# STM32F407VET6.net
KiCad netlist of a schematic drawn in Altium Designer
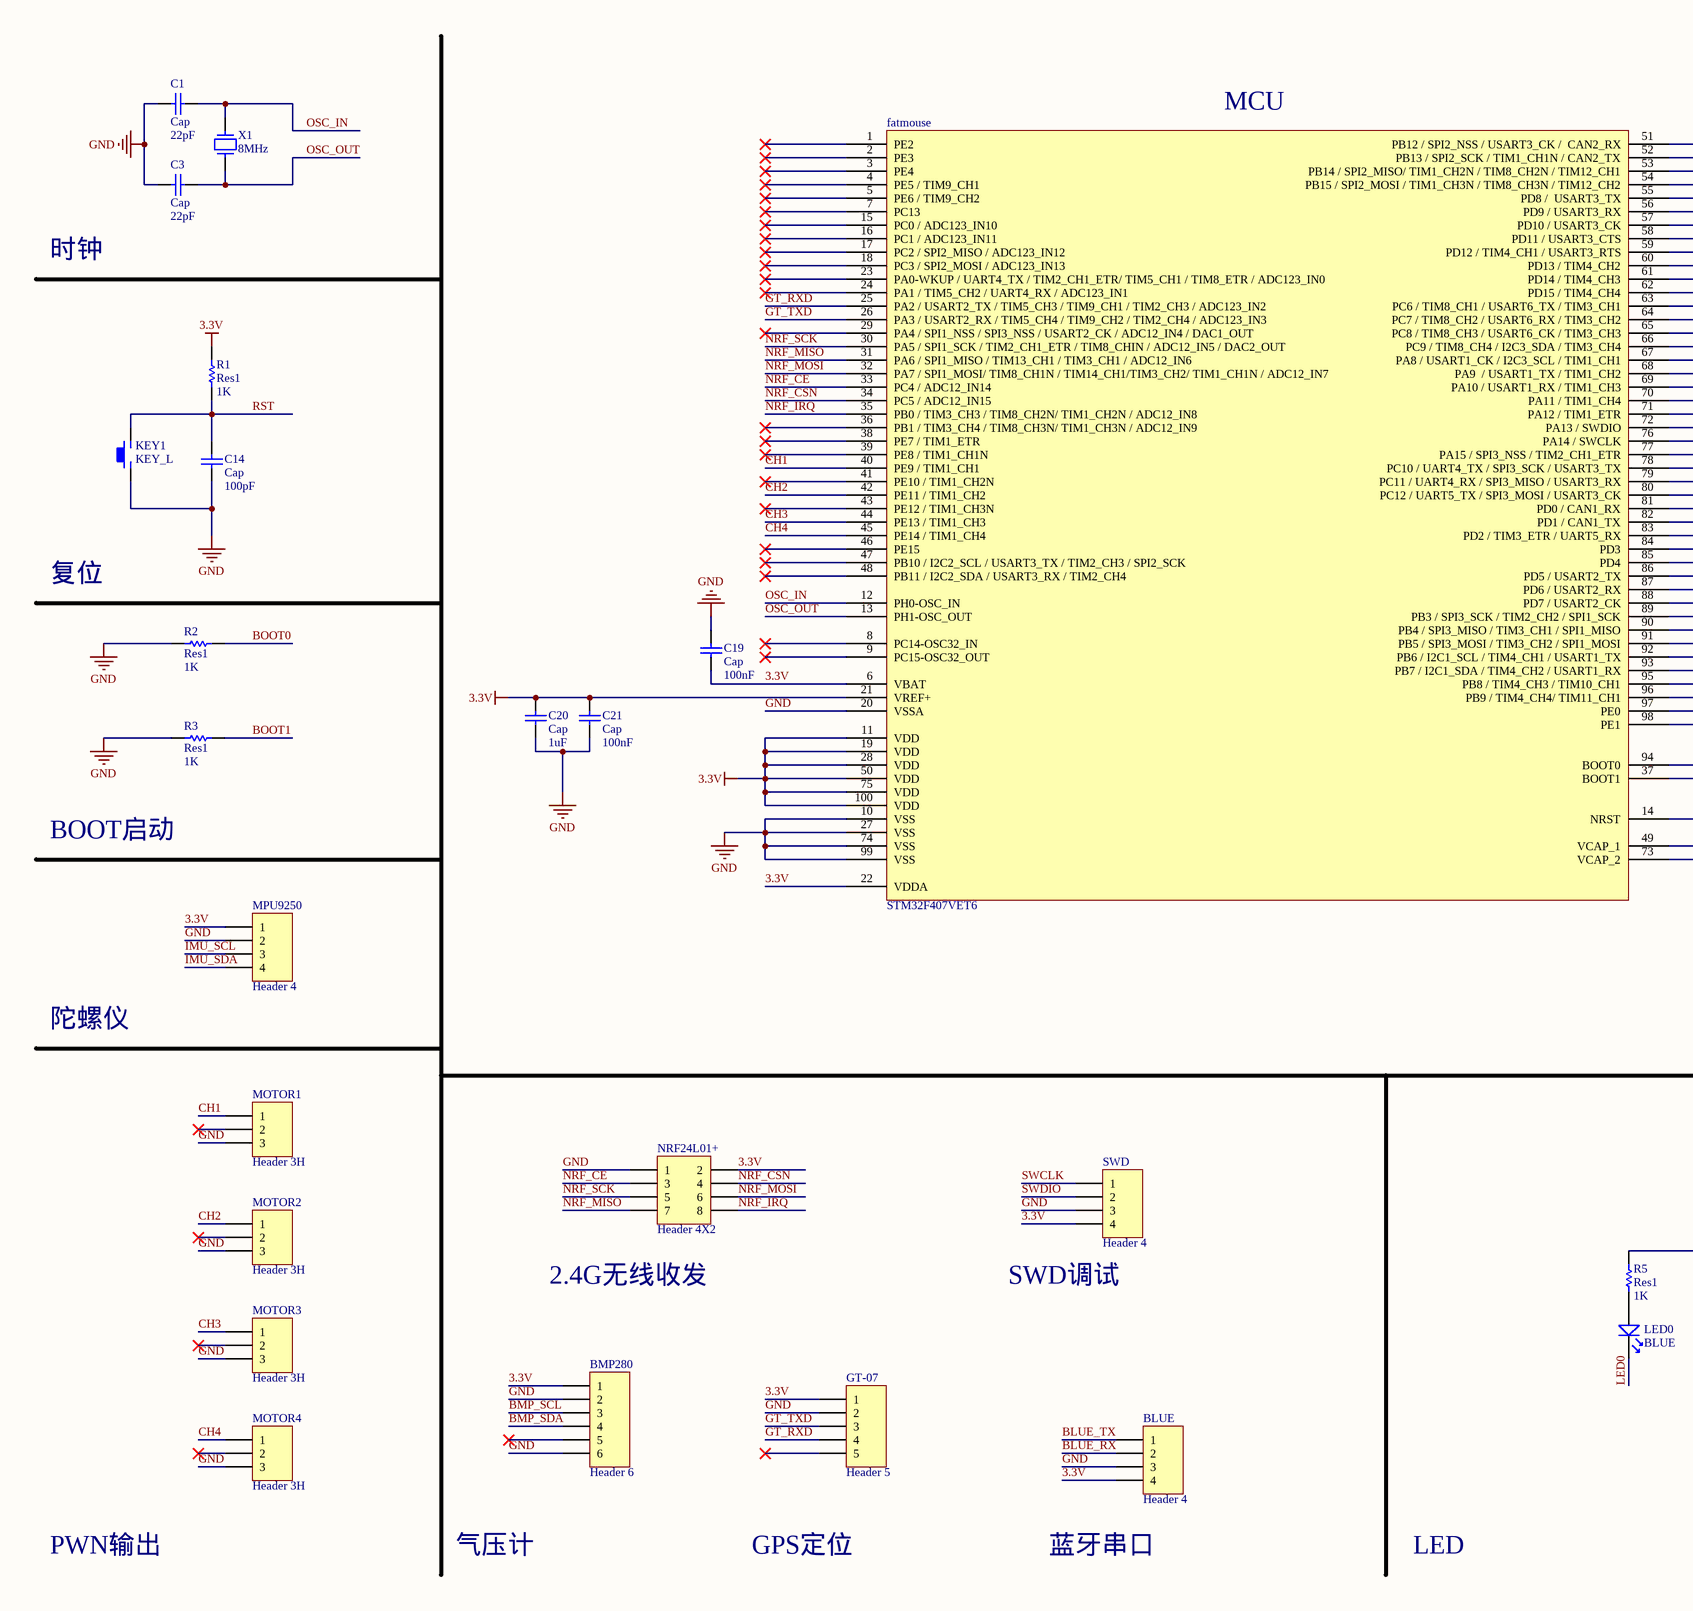
[diagram p0: STM32F407VET6.SchDoc, left]
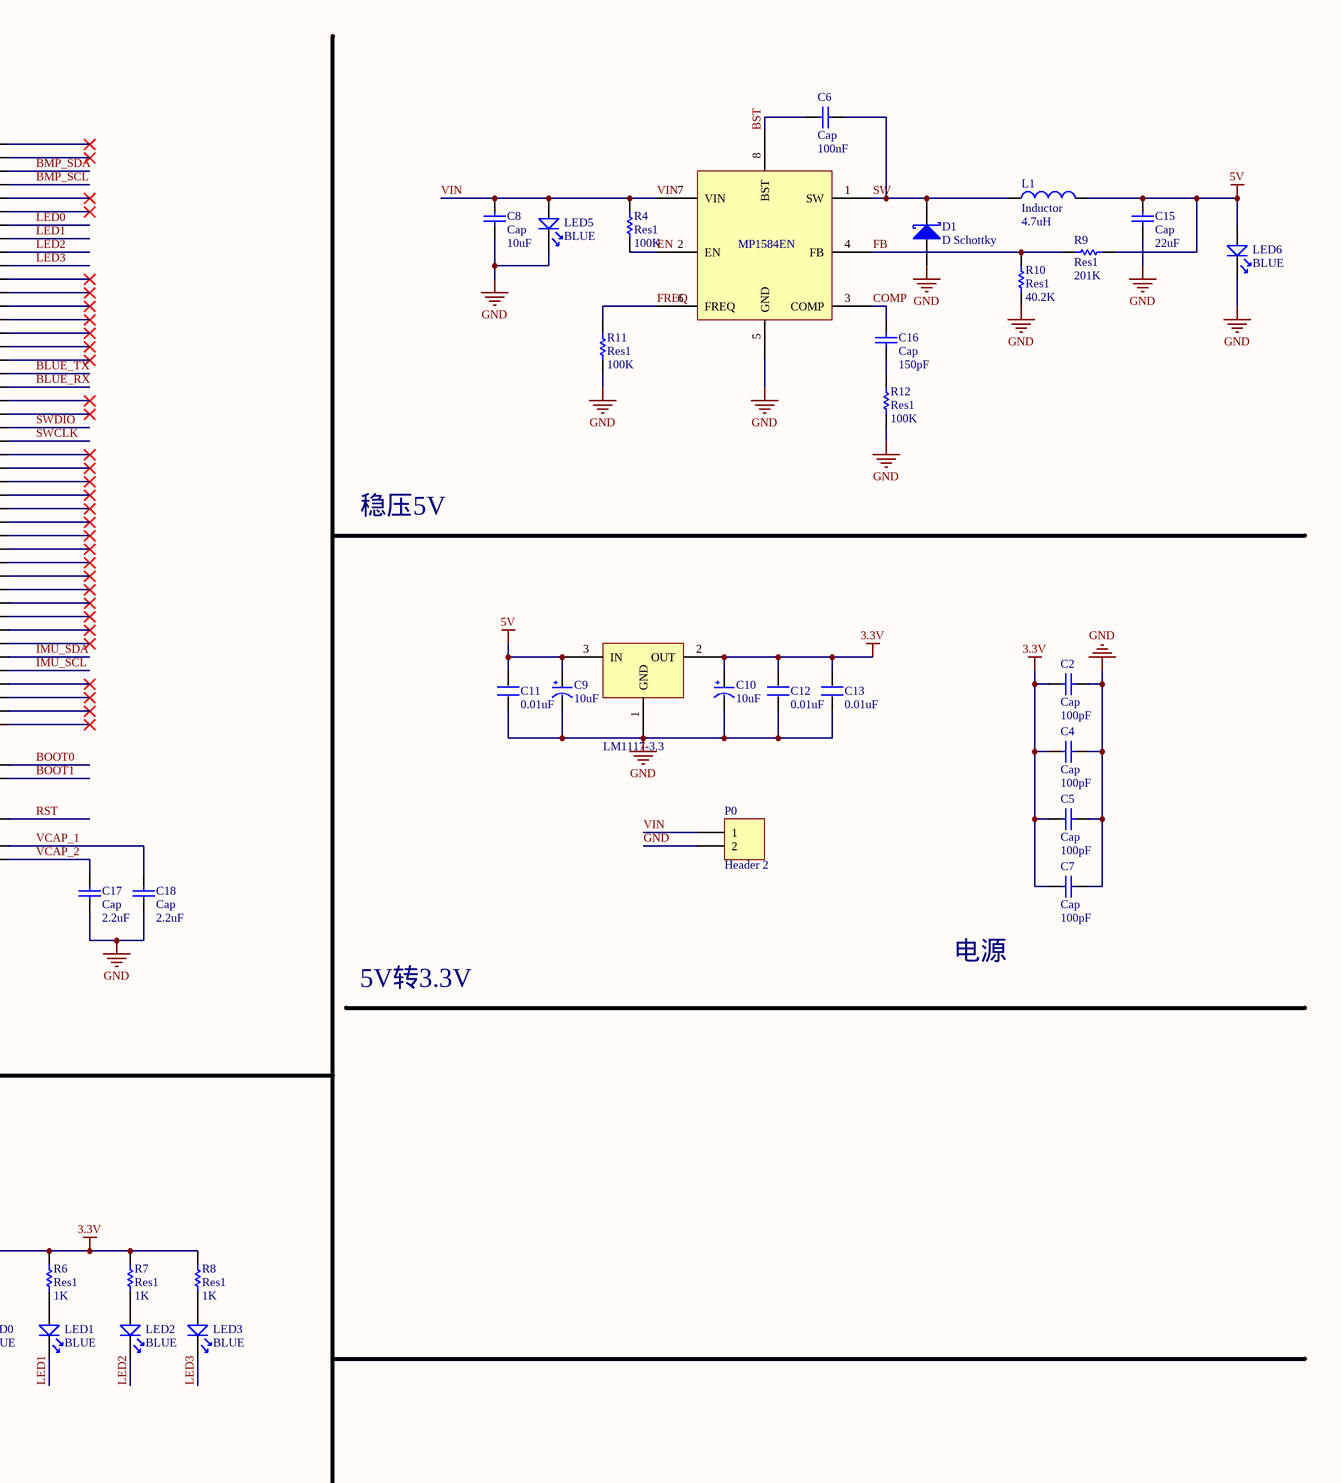
[diagram p1: STM32F407VET6.SchDoc, right]

(export (version "E")
  (design (tool "Eeschema 10.0.6"))
  (components
    (comp (ref "5V-3.3V")
      (value "LM1117-3.3")
      (footprint "SOT223_M")
      (libsource (lib "QUA") (part "LM1117-3.3"))
    )
    (comp (ref "BLUE")
      (value "Header 4")
      (footprint "PIN-4-2.54-1.0")
      (description "Header, 4-Pin")
      (fields (field (name "PUBLISHER") "Altium Limited"))
      (libsource (lib "Miscellaneous Connectors") (part "Header 4"))
    )
    (comp (ref "BMP280")
      (value "Header 6")
      (footprint "HDR1X6")
      (description "Header, 6-Pin")
      (fields (field (name "PUBLISHER") "Altium Limited"))
      (libsource (lib "Miscellaneous Connectors") (part "Header 6"))
    )
    (comp (ref "C1")
      (value "Cap")
      (footprint "C 0805")
      (description "Capacitor")
      (fields (field (name "ALTIUM_VALUE") "22pF") (field (name "PUBLISHER") "Altium Limited"))
      (libsource (lib "Miscellaneous Devices") (part "Cap"))
    )
    (comp (ref "C2")
      (value "Cap")
      (footprint "C 0805")
      (description "Capacitor")
      (fields (field (name "ALTIUM_VALUE") "100pF") (field (name "PUBLISHER") "Altium Limited"))
      (libsource (lib "Miscellaneous Devices") (part "Cap"))
    )
    (comp (ref "C3")
      (value "Cap")
      (footprint "C 0805")
      (description "Capacitor")
      (fields (field (name "ALTIUM_VALUE") "22pF") (field (name "PUBLISHER") "Altium Limited"))
      (libsource (lib "Miscellaneous Devices") (part "Cap"))
    )
    (comp (ref "C4")
      (value "Cap")
      (footprint "C 0805")
      (description "Capacitor")
      (fields (field (name "ALTIUM_VALUE") "100pF") (field (name "PUBLISHER") "Altium Limited"))
      (libsource (lib "Miscellaneous Devices") (part "Cap"))
    )
    (comp (ref "C5")
      (value "Cap")
      (footprint "C 0805")
      (description "Capacitor")
      (fields (field (name "ALTIUM_VALUE") "100pF") (field (name "PUBLISHER") "Altium Limited"))
      (libsource (lib "Miscellaneous Devices") (part "Cap"))
    )
    (comp (ref "C6")
      (value "Cap")
      (footprint "C 0805")
      (description "Capacitor")
      (fields (field (name "ALTIUM_VALUE") "100nF") (field (name "PUBLISHER") "Altium Limited"))
      (libsource (lib "Miscellaneous Devices") (part "Cap"))
    )
    (comp (ref "C7")
      (value "Cap")
      (footprint "C 0805")
      (description "Capacitor")
      (fields (field (name "ALTIUM_VALUE") "100pF") (field (name "PUBLISHER") "Altium Limited"))
      (libsource (lib "Miscellaneous Devices") (part "Cap"))
    )
    (comp (ref "C8")
      (value "Cap")
      (footprint "C 0805")
      (description "Capacitor")
      (fields (field (name "ALTIUM_VALUE") "10uF") (field (name "PUBLISHER") "Altium Limited"))
      (libsource (lib "Miscellaneous Devices") (part "Cap"))
    )
    (comp (ref "C9") (value "10uF") (footprint "CD A(3216)") (libsource (lib "REMOTOR V1.6") (part "CAP")))
    (comp (ref "C10") (value "10uF") (footprint "CD A(3216)") (libsource (lib "REMOTOR V1.6") (part "CAP")))
    (comp (ref "C11") (value "0.01uF") (footprint "C 0805") (libsource (lib "REMOTOR V1.6") (part "C")))
    (comp (ref "C12") (value "0.01uF") (footprint "C 0805") (libsource (lib "REMOTOR V1.6") (part "C")))
    (comp (ref "C13") (value "0.01uF") (footprint "C 0805") (libsource (lib "REMOTOR V1.6") (part "C")))
    (comp (ref "C14")
      (value "Cap")
      (footprint "C 0805")
      (description "Capacitor")
      (fields (field (name "ALTIUM_VALUE") "100pF") (field (name "PUBLISHER") "Altium Limited"))
      (libsource (lib "Miscellaneous Devices") (part "Cap"))
    )
    (comp (ref "C15")
      (value "Cap")
      (footprint "C 0805")
      (description "Capacitor")
      (fields (field (name "ALTIUM_VALUE") "22uF") (field (name "PUBLISHER") "Altium Limited"))
      (libsource (lib "Miscellaneous Devices") (part "Cap"))
    )
    (comp (ref "C16")
      (value "Cap")
      (footprint "C 0805")
      (description "Capacitor")
      (fields (field (name "ALTIUM_VALUE") "150pF") (field (name "PUBLISHER") "Altium Limited"))
      (libsource (lib "Miscellaneous Devices") (part "Cap"))
    )
    (comp (ref "C17")
      (value "Cap")
      (footprint "C 0805")
      (description "Capacitor")
      (fields (field (name "ALTIUM_VALUE") "2.2uF") (field (name "PUBLISHER") "Altium Limited"))
      (libsource (lib "Miscellaneous Devices") (part "Cap"))
    )
    (comp (ref "C18")
      (value "Cap")
      (footprint "C 0805")
      (description "Capacitor")
      (fields (field (name "ALTIUM_VALUE") "2.2uF") (field (name "PUBLISHER") "Altium Limited"))
      (libsource (lib "Miscellaneous Devices") (part "Cap"))
    )
    (comp (ref "C19")
      (value "Cap")
      (footprint "C 0805")
      (description "Capacitor")
      (fields (field (name "ALTIUM_VALUE") "100nF") (field (name "PUBLISHER") "Altium Limited"))
      (libsource (lib "Miscellaneous Devices") (part "Cap"))
    )
    (comp (ref "C20")
      (value "Cap")
      (footprint "C 0805")
      (description "Capacitor")
      (fields (field (name "ALTIUM_VALUE") "1uF") (field (name "PUBLISHER") "Altium Limited"))
      (libsource (lib "Miscellaneous Devices") (part "Cap"))
    )
    (comp (ref "C21")
      (value "Cap")
      (footprint "C 0805")
      (description "Capacitor")
      (fields (field (name "ALTIUM_VALUE") "100nF") (field (name "PUBLISHER") "Altium Limited"))
      (libsource (lib "Miscellaneous Devices") (part "Cap"))
    )
    (comp (ref "D1")
      (value "D Schottky")
      (footprint "SMA")
      (description "Schottky Diode")
      (fields (field (name "PUBLISHER") "Altium Limited"))
      (libsource (lib "Miscellaneous Devices") (part "D Schottky"))
    )
    (comp (ref "fatmouse")
      (value "STM32F407VET6")
      (footprint "QFP-100-0.5")
      (libsource (lib "QUA") (part "STM32F407VET6"))
    )
    (comp (ref "GT-07")
      (value "Header 5")
      (footprint "HDR1X5")
      (description "Header, 5-Pin")
      (fields (field (name "PUBLISHER") "Altium Limited"))
      (libsource (lib "Miscellaneous Connectors") (part "Header 5"))
    )
    (comp (ref "KEY1") (value "KEY_L") (footprint "key") (libsource (lib "REMOTOR V1.6") (part "KEY")))
    (comp (ref "L1")
      (value "Inductor")
      (footprint "CDRH74")
      (fields (field (name "ALTIUM_VALUE") "4.7uH") (field (name "PUBLISHER") "Altium Limited"))
      (libsource (lib "Miscellaneous Devices") (part "Inductor"))
    )
    (comp (ref "LED0") (value "BLUE") (footprint "LED-0805") (libsource (lib "REMOTOR V1.6") (part "LED")))
    (comp (ref "LED1") (value "BLUE") (footprint "LED-0805") (libsource (lib "REMOTOR V1.6") (part "LED")))
    (comp (ref "LED2") (value "BLUE") (footprint "LED-0805") (libsource (lib "REMOTOR V1.6") (part "LED")))
    (comp (ref "LED3") (value "BLUE") (footprint "LED-0805") (libsource (lib "REMOTOR V1.6") (part "LED")))
    (comp (ref "LED5") (value "BLUE") (footprint "LED-0805") (libsource (lib "REMOTOR V1.6") (part "LED")))
    (comp (ref "LED6") (value "BLUE") (footprint "LED-0805") (libsource (lib "REMOTOR V1.6") (part "LED")))
    (comp (ref "MOTOR1")
      (value "Header 3H")
      (footprint "HDR1X3H")
      (description "Header, 3-Pin, Right Angle")
      (fields (field (name "PUBLISHER") "Altium Limited"))
      (libsource (lib "Miscellaneous Connectors") (part "Header 3H"))
    )
    (comp (ref "MOTOR2")
      (value "Header 3H")
      (footprint "HDR1X3H")
      (description "Header, 3-Pin, Right Angle")
      (fields (field (name "PUBLISHER") "Altium Limited"))
      (libsource (lib "Miscellaneous Connectors") (part "Header 3H"))
    )
    (comp (ref "MOTOR3")
      (value "Header 3H")
      (footprint "HDR1X3H")
      (description "Header, 3-Pin, Right Angle")
      (fields (field (name "PUBLISHER") "Altium Limited"))
      (libsource (lib "Miscellaneous Connectors") (part "Header 3H"))
    )
    (comp (ref "MOTOR4")
      (value "Header 3H")
      (footprint "HDR1X3H")
      (description "Header, 3-Pin, Right Angle")
      (fields (field (name "PUBLISHER") "Altium Limited"))
      (libsource (lib "Miscellaneous Connectors") (part "Header 3H"))
    )
    (comp (ref "MP1584EN")
      (value "MP1584EN")
      (footprint "LC-SOIC-8_EP_150mil")
      (libsource (lib "QUA") (part "MP1584EN"))
    )
    (comp (ref "MPU9250")
      (value "Header 4")
      (footprint "HDR1X4")
      (description "Header, 4-Pin")
      (fields (field (name "PUBLISHER") "Altium Limited"))
      (libsource (lib "Miscellaneous Connectors") (part "Header 4"))
    )
    (comp (ref "NRF24L01+")
      (value "Header 4X2")
      (footprint "HDR2X4")
      (description "Header, 4-Pin, Dual row")
      (fields (field (name "PUBLISHER") "Altium Limited"))
      (libsource (lib "Miscellaneous Connectors") (part "Header 4X2"))
    )
    (comp (ref "P0")
      (value "Header 2")
      (footprint "xt30")
      (description "Header, 2-Pin")
      (fields (field (name "PUBLISHER") "Altium Limited"))
      (libsource (lib "Miscellaneous Connectors") (part "Header 2"))
    )
    (comp (ref "R1")
      (value "Res1")
      (footprint "0805")
      (description "Resistor")
      (fields (field (name "ALTIUM_VALUE") "1K") (field (name "PUBLISHER") "Altium Limited"))
      (libsource (lib "Miscellaneous Devices") (part "Res1"))
    )
    (comp (ref "R2")
      (value "Res1")
      (footprint "0805")
      (description "Resistor")
      (fields (field (name "ALTIUM_VALUE") "1K") (field (name "PUBLISHER") "Altium Limited"))
      (libsource (lib "Miscellaneous Devices") (part "Res1"))
    )
    (comp (ref "R3")
      (value "Res1")
      (footprint "0805")
      (description "Resistor")
      (fields (field (name "ALTIUM_VALUE") "1K") (field (name "PUBLISHER") "Altium Limited"))
      (libsource (lib "Miscellaneous Devices") (part "Res1"))
    )
    (comp (ref "R4")
      (value "Res1")
      (footprint "0805")
      (description "Resistor")
      (fields (field (name "ALTIUM_VALUE") "100K") (field (name "PUBLISHER") "Altium Limited"))
      (libsource (lib "Miscellaneous Devices") (part "Res1"))
    )
    (comp (ref "R5")
      (value "Res1")
      (footprint "0805")
      (description "Resistor")
      (fields (field (name "ALTIUM_VALUE") "1K") (field (name "PUBLISHER") "Altium Limited"))
      (libsource (lib "Miscellaneous Devices") (part "Res1"))
    )
    (comp (ref "R6")
      (value "Res1")
      (footprint "0805")
      (description "Resistor")
      (fields (field (name "ALTIUM_VALUE") "1K") (field (name "PUBLISHER") "Altium Limited"))
      (libsource (lib "Miscellaneous Devices") (part "Res1"))
    )
    (comp (ref "R7")
      (value "Res1")
      (footprint "0805")
      (description "Resistor")
      (fields (field (name "ALTIUM_VALUE") "1K") (field (name "PUBLISHER") "Altium Limited"))
      (libsource (lib "Miscellaneous Devices") (part "Res1"))
    )
    (comp (ref "R8")
      (value "Res1")
      (footprint "0805")
      (description "Resistor")
      (fields (field (name "ALTIUM_VALUE") "1K") (field (name "PUBLISHER") "Altium Limited"))
      (libsource (lib "Miscellaneous Devices") (part "Res1"))
    )
    (comp (ref "R9")
      (value "Res1")
      (footprint "0805")
      (description "Resistor")
      (fields (field (name "ALTIUM_VALUE") "201K") (field (name "PUBLISHER") "Altium Limited"))
      (libsource (lib "Miscellaneous Devices") (part "Res1"))
    )
    (comp (ref "R10")
      (value "Res1")
      (footprint "0805")
      (description "Resistor")
      (fields (field (name "ALTIUM_VALUE") "40.2K") (field (name "PUBLISHER") "Altium Limited"))
      (libsource (lib "Miscellaneous Devices") (part "Res1"))
    )
    (comp (ref "R11")
      (value "Res1")
      (footprint "0805")
      (description "Resistor")
      (fields (field (name "ALTIUM_VALUE") "100K") (field (name "PUBLISHER") "Altium Limited"))
      (libsource (lib "Miscellaneous Devices") (part "Res1"))
    )
    (comp (ref "R12")
      (value "Res1")
      (footprint "0805")
      (description "Resistor")
      (fields (field (name "ALTIUM_VALUE") "100K") (field (name "PUBLISHER") "Altium Limited"))
      (libsource (lib "Miscellaneous Devices") (part "Res1"))
    )
    (comp (ref "SWD")
      (value "Header 4")
      (footprint "PIN-4-2.54-1.0")
      (description "Header, 4-Pin")
      (fields (field (name "PUBLISHER") "Altium Limited"))
      (libsource (lib "Miscellaneous Connectors") (part "Header 4"))
    )
    (comp (ref "X1")
      (value "8MHz")
      (footprint "HC49S")
      (description "Crystal")
      (libsource (lib "General") (part "XTAL-2"))
    )
  )
  (nets
    (net (code "1") (name "/BLUE_RX") (class "Default")
      (node (ref "BLUE") (pin "2") (pinfunction "2_2") (pintype "passive"))
      (node (ref "fatmouse") (pin "69") (pinfunction "PA10_/_USART1_RX_/_TIM1_CH3_69") (pintype "passive"))
    )
    (net (code "2") (name "/BLUE_TX") (class "Default")
      (node (ref "BLUE") (pin "1") (pinfunction "1_1") (pintype "passive"))
      (node (ref "fatmouse") (pin "68") (pinfunction "PA9__/_USART1_TX_/_TIM1_CH2_68") (pintype "passive"))
    )
    (net (code "3") (name "/BMP_SCL") (class "Default")
      (node (ref "BMP280") (pin "3") (pinfunction "3_3") (pintype "passive"))
      (node (ref "fatmouse") (pin "54") (pinfunction "PB15_/_SPI2_MOSI_/_TIM1_CH3N_/_TIM8_CH3N_/_TIM12_CH2_54") (pintype "passive"))
    )
    (net (code "4") (name "/BMP_SDA") (class "Default")
      (node (ref "BMP280") (pin "4") (pinfunction "4_4") (pintype "passive"))
      (node (ref "fatmouse") (pin "53") (pinfunction "PB14_/_SPI2_MISO/_TIM1_CH2N_/_TIM8_CH2N_/_TIM12_CH1_53") (pintype "passive"))
    )
    (net (code "5") (name "/BOOT0") (class "Default")
      (node (ref "R2") (pin "2") (pinfunction "2_2") (pintype "passive"))
      (node (ref "fatmouse") (pin "94") (pinfunction "BOOT0_94") (pintype "passive"))
    )
    (net (code "6") (name "/BOOT1") (class "Default")
      (node (ref "R3") (pin "2") (pinfunction "2_2") (pintype "passive"))
      (node (ref "fatmouse") (pin "37") (pinfunction "BOOT1_37") (pintype "passive"))
    )
    (net (code "7") (name "/BST") (class "Default")
      (node (ref "C6") (pin "1") (pinfunction "1_1") (pintype "passive"))
      (node (ref "MP1584EN") (pin "8") (pinfunction "BST_8") (pintype "passive"))
    )
    (net (code "8") (name "/CH1") (class "Default")
      (node (ref "MOTOR1") (pin "1") (pinfunction "1_1") (pintype "passive"))
      (node (ref "fatmouse") (pin "40") (pinfunction "PE9_/_TIM1_CH1_40") (pintype "passive"))
    )
    (net (code "9") (name "/CH2") (class "Default")
      (node (ref "MOTOR2") (pin "1") (pinfunction "1_1") (pintype "passive"))
      (node (ref "fatmouse") (pin "42") (pinfunction "PE11_/_TIM1_CH2_42") (pintype "passive"))
    )
    (net (code "10") (name "/CH3") (class "Default")
      (node (ref "MOTOR3") (pin "1") (pinfunction "1_1") (pintype "passive"))
      (node (ref "fatmouse") (pin "44") (pinfunction "PE13_/_TIM1_CH3_44") (pintype "passive"))
    )
    (net (code "11") (name "/CH4") (class "Default")
      (node (ref "MOTOR4") (pin "1") (pinfunction "1_1") (pintype "passive"))
      (node (ref "fatmouse") (pin "45") (pinfunction "PE14_/_TIM1_CH4_45") (pintype "passive"))
    )
    (net (code "12") (name "/COMP") (class "Default")
      (node (ref "C16") (pin "2") (pinfunction "2_2") (pintype "passive"))
      (node (ref "MP1584EN") (pin "3") (pinfunction "COMP_3") (pintype "passive"))
    )
    (net (code "13") (name "/EN") (class "Default")
      (node (ref "MP1584EN") (pin "2") (pinfunction "EN_2") (pintype "passive"))
      (node (ref "R4") (pin "1") (pinfunction "1_1") (pintype "passive"))
    )
    (net (code "14") (name "/FB") (class "Default")
      (node (ref "MP1584EN") (pin "4") (pinfunction "FB_4") (pintype "passive"))
      (node (ref "R10") (pin "2") (pinfunction "2_2") (pintype "passive"))
      (node (ref "R9") (pin "2") (pinfunction "2_2") (pintype "passive"))
    )
    (net (code "15") (name "/FREQ") (class "Default")
      (node (ref "MP1584EN") (pin "6") (pinfunction "FREQ_6") (pintype "passive"))
      (node (ref "R11") (pin "2") (pinfunction "2_2") (pintype "passive"))
    )
    (net (code "16") (name "/GT_RXD") (class "Default")
      (node (ref "GT-07") (pin "4") (pinfunction "4_4") (pintype "passive"))
      (node (ref "fatmouse") (pin "25") (pinfunction "PA2_/_USART2_TX_/_TIM5_CH3_/_TIM9_CH1_/_TIM2_CH3_/_ADC123_IN2_25") (pintype "passive"))
    )
    (net (code "17") (name "/GT_TXD") (class "Default")
      (node (ref "GT-07") (pin "3") (pinfunction "3_3") (pintype "passive"))
      (node (ref "fatmouse") (pin "26") (pinfunction "PA3_/_USART2_RX_/_TIM5_CH4_/_TIM9_CH2_/_TIM2_CH4_/_ADC123_IN3_26") (pintype "passive"))
    )
    (net (code "18") (name "/IMU_SCL") (class "Default")
      (node (ref "MPU9250") (pin "3") (pinfunction "3_3") (pintype "passive"))
      (node (ref "fatmouse") (pin "93") (pinfunction "PB7_/_I2C1_SDA_/_TIM4_CH2_/_USART1_RX_93") (pintype "passive"))
    )
    (net (code "19") (name "/IMU_SDA") (class "Default")
      (node (ref "MPU9250") (pin "4") (pinfunction "4_4") (pintype "passive"))
      (node (ref "fatmouse") (pin "92") (pinfunction "PB6_/_I2C1_SCL_/_TIM4_CH1_/_USART1_TX_92") (pintype "passive"))
    )
    (net (code "20") (name "/LED0") (class "Default")
      (node (ref "LED0") (pin "2") (pinfunction "2_2") (pintype "passive"))
      (node (ref "fatmouse") (pin "57") (pinfunction "PD10_/_USART3_CK_57") (pintype "passive"))
    )
    (net (code "21") (name "/LED1") (class "Default")
      (node (ref "LED1") (pin "2") (pinfunction "2_2") (pintype "passive"))
      (node (ref "fatmouse") (pin "58") (pinfunction "PD11_/_USART3_CTS_58") (pintype "passive"))
    )
    (net (code "22") (name "/LED2") (class "Default")
      (node (ref "LED2") (pin "2") (pinfunction "2_2") (pintype "passive"))
      (node (ref "fatmouse") (pin "59") (pinfunction "PD12_/_TIM4_CH1_/_USART3_RTS_59") (pintype "passive"))
    )
    (net (code "23") (name "/LED3") (class "Default")
      (node (ref "LED3") (pin "2") (pinfunction "2_2") (pintype "passive"))
      (node (ref "fatmouse") (pin "60") (pinfunction "PD13_/_TIM4_CH2_60") (pintype "passive"))
    )
    (net (code "24") (name "/NRF_CE") (class "Default")
      (node (ref "NRF24L01+") (pin "3") (pinfunction "3_3") (pintype "passive"))
      (node (ref "fatmouse") (pin "33") (pinfunction "PC4_/_ADC12_IN14_33") (pintype "passive"))
    )
    (net (code "25") (name "/NRF_CSN") (class "Default")
      (node (ref "NRF24L01+") (pin "4") (pinfunction "4_4") (pintype "passive"))
      (node (ref "fatmouse") (pin "34") (pinfunction "PC5_/_ADC12_IN15_34") (pintype "passive"))
    )
    (net (code "26") (name "/NRF_IRQ") (class "Default")
      (node (ref "NRF24L01+") (pin "8") (pinfunction "8_8") (pintype "passive"))
      (node (ref "fatmouse") (pin "35") (pinfunction "PB0_/_TIM3_CH3_/_TIM8_CH2N/_TIM1_CH2N_/_ADC12_IN8_35") (pintype "passive"))
    )
    (net (code "27") (name "/NRF_MISO") (class "Default")
      (node (ref "NRF24L01+") (pin "7") (pinfunction "7_7") (pintype "passive"))
      (node (ref "fatmouse") (pin "31") (pinfunction "PA6_/_SPI1_MISO_/_TIM13_CH1_/_TIM3_CH1_/_ADC12_IN6_31") (pintype "passive"))
    )
    (net (code "28") (name "/NRF_MOSI") (class "Default")
      (node (ref "NRF24L01+") (pin "6") (pinfunction "6_6") (pintype "passive"))
      (node (ref "fatmouse") (pin "32") (pinfunction "PA7_/_SPI1_MOSI/_TIM8_CH1N_/_TIM14_CH1/TIM3_CH2/_TIM1_CH1N_/_ADC12_IN7_32") (pintype "passive"))
    )
    (net (code "29") (name "/NRF_SCK") (class "Default")
      (node (ref "NRF24L01+") (pin "5") (pinfunction "5_5") (pintype "passive"))
      (node (ref "fatmouse") (pin "30") (pinfunction "PA5_/_SPI1_SCK_/_TIM2_CH1_ETR_/_TIM8_CHIN_/_ADC12_IN5_/_DAC2_OUT_30") (pintype "passive"))
    )
    (net (code "30") (name "/OSC_IN") (class "Default")
      (node (ref "C1") (pin "2") (pinfunction "2_2") (pintype "passive"))
      (node (ref "X1") (pin "1") (pinfunction "1_1") (pintype "passive"))
      (node (ref "fatmouse") (pin "12") (pinfunction "PH0-OSC_IN_12") (pintype "passive"))
    )
    (net (code "31") (name "/OSC_OUT") (class "Default")
      (node (ref "C3") (pin "2") (pinfunction "2_2") (pintype "passive"))
      (node (ref "X1") (pin "2") (pinfunction "2_2") (pintype "passive"))
      (node (ref "fatmouse") (pin "13") (pinfunction "PH1-OSC_OUT_13") (pintype "passive"))
    )
    (net (code "32") (name "/RST") (class "Default")
      (node (ref "C14") (pin "2") (pinfunction "2_2") (pintype "passive"))
      (node (ref "KEY1") (pin "2") (pinfunction "2_2") (pintype "passive"))
      (node (ref "R1") (pin "1") (pinfunction "1_1") (pintype "passive"))
      (node (ref "fatmouse") (pin "14") (pinfunction "NRST_14") (pintype "passive"))
    )
    (net (code "33") (name "/SW") (class "Default")
      (node (ref "C6") (pin "2") (pinfunction "2_2") (pintype "passive"))
      (node (ref "D1") (pin "2") (pinfunction "K_2") (pintype "passive"))
      (node (ref "L1") (pin "1") (pinfunction "1_1") (pintype "passive"))
      (node (ref "MP1584EN") (pin "1") (pinfunction "SW_1") (pintype "passive"))
    )
    (net (code "34") (name "/SWCLK") (class "Default")
      (node (ref "SWD") (pin "1") (pinfunction "1_1") (pintype "passive"))
      (node (ref "fatmouse") (pin "76") (pinfunction "PA14_/_SWCLK_76") (pintype "passive"))
    )
    (net (code "35") (name "/SWDIO") (class "Default")
      (node (ref "SWD") (pin "2") (pinfunction "2_2") (pintype "passive"))
      (node (ref "fatmouse") (pin "72") (pinfunction "PA13_/_SWDIO_72") (pintype "passive"))
    )
    (net (code "36") (name "/VCAP_1") (class "Default")
      (node (ref "C18") (pin "1") (pinfunction "1_1") (pintype "passive"))
      (node (ref "fatmouse") (pin "49") (pinfunction "VCAP_1_49") (pintype "passive"))
    )
    (net (code "37") (name "/VCAP_2") (class "Default")
      (node (ref "C17") (pin "1") (pinfunction "1_1") (pintype "passive"))
      (node (ref "fatmouse") (pin "73") (pinfunction "VCAP_2_73") (pintype "passive"))
    )
    (net (code "38") (name "/VIN") (class "Default")
      (node (ref "C8") (pin "1") (pinfunction "1_1") (pintype "passive"))
      (node (ref "LED5") (pin "1") (pinfunction "1_1") (pintype "passive"))
      (node (ref "MP1584EN") (pin "7") (pinfunction "VIN_7") (pintype "passive"))
      (node (ref "P0") (pin "1") (pinfunction "1_1") (pintype "passive"))
      (node (ref "R4") (pin "2") (pinfunction "2_2") (pintype "passive"))
    )
    (net (code "39") (name "3.3V") (class "Default")
      (node (ref "5V-3.3V") (pin "2") (pinfunction "OUT_2") (pintype "passive"))
      (node (ref "BLUE") (pin "4") (pinfunction "4_4") (pintype "passive"))
      (node (ref "BMP280") (pin "1") (pinfunction "1_1") (pintype "passive"))
      (node (ref "C10") (pin "1") (pinfunction "VCC_1") (pintype "passive"))
      (node (ref "C12") (pin "2") (pintype "passive"))
      (node (ref "C13") (pin "2") (pintype "passive"))
      (node (ref "C19") (pin "1") (pinfunction "1_1") (pintype "passive"))
      (node (ref "C2") (pin "1") (pinfunction "1_1") (pintype "passive"))
      (node (ref "C20") (pin "2") (pinfunction "2_2") (pintype "passive"))
      (node (ref "C21") (pin "2") (pinfunction "2_2") (pintype "passive"))
      (node (ref "C4") (pin "1") (pinfunction "1_1") (pintype "passive"))
      (node (ref "C5") (pin "1") (pinfunction "1_1") (pintype "passive"))
      (node (ref "C7") (pin "1") (pinfunction "1_1") (pintype "passive"))
      (node (ref "GT-07") (pin "1") (pinfunction "1_1") (pintype "passive"))
      (node (ref "MPU9250") (pin "1") (pinfunction "1_1") (pintype "passive"))
      (node (ref "NRF24L01+") (pin "2") (pinfunction "2_2") (pintype "passive"))
      (node (ref "R1") (pin "2") (pinfunction "2_2") (pintype "passive"))
      (node (ref "R5") (pin "2") (pinfunction "2_2") (pintype "passive"))
      (node (ref "R6") (pin "2") (pinfunction "2_2") (pintype "passive"))
      (node (ref "R7") (pin "2") (pinfunction "2_2") (pintype "passive"))
      (node (ref "R8") (pin "2") (pinfunction "2_2") (pintype "passive"))
      (node (ref "SWD") (pin "4") (pinfunction "4_4") (pintype "passive"))
      (node (ref "fatmouse") (pin "100") (pinfunction "VDD_100") (pintype "passive"))
      (node (ref "fatmouse") (pin "11") (pinfunction "VDD_11") (pintype "passive"))
      (node (ref "fatmouse") (pin "19") (pinfunction "VDD_19") (pintype "passive"))
      (node (ref "fatmouse") (pin "21") (pinfunction "VREF+_21") (pintype "passive"))
      (node (ref "fatmouse") (pin "22") (pinfunction "VDDA_22") (pintype "passive"))
      (node (ref "fatmouse") (pin "28") (pinfunction "VDD_28") (pintype "passive"))
      (node (ref "fatmouse") (pin "50") (pinfunction "VDD_50") (pintype "passive"))
      (node (ref "fatmouse") (pin "6") (pinfunction "VBAT_6") (pintype "passive"))
      (node (ref "fatmouse") (pin "75") (pinfunction "VDD_75") (pintype "passive"))
    )
    (net (code "40") (name "5V") (class "Default")
      (node (ref "5V-3.3V") (pin "3") (pinfunction "IN_3") (pintype "passive"))
      (node (ref "C11") (pin "2") (pintype "passive"))
      (node (ref "C15") (pin "1") (pinfunction "1_1") (pintype "passive"))
      (node (ref "C9") (pin "1") (pinfunction "VCC_1") (pintype "passive"))
      (node (ref "L1") (pin "2") (pinfunction "2_2") (pintype "passive"))
      (node (ref "LED6") (pin "1") (pinfunction "1_1") (pintype "passive"))
      (node (ref "R9") (pin "1") (pinfunction "1_1") (pintype "passive"))
    )
    (net (code "41") (name "GND") (class "Default")
      (node (ref "5V-3.3V") (pin "1") (pinfunction "GND_1") (pintype "passive"))
      (node (ref "BLUE") (pin "3") (pinfunction "3_3") (pintype "passive"))
      (node (ref "BMP280") (pin "2") (pinfunction "2_2") (pintype "passive"))
      (node (ref "BMP280") (pin "6") (pinfunction "6_6") (pintype "passive"))
      (node (ref "C1") (pin "1") (pinfunction "1_1") (pintype "passive"))
      (node (ref "C10") (pin "2") (pinfunction "GND_2") (pintype "passive"))
      (node (ref "C11") (pin "1") (pintype "passive"))
      (node (ref "C12") (pin "1") (pintype "passive"))
      (node (ref "C13") (pin "1") (pintype "passive"))
      (node (ref "C14") (pin "1") (pinfunction "1_1") (pintype "passive"))
      (node (ref "C15") (pin "2") (pinfunction "2_2") (pintype "passive"))
      (node (ref "C17") (pin "2") (pinfunction "2_2") (pintype "passive"))
      (node (ref "C18") (pin "2") (pinfunction "2_2") (pintype "passive"))
      (node (ref "C19") (pin "2") (pinfunction "2_2") (pintype "passive"))
      (node (ref "C2") (pin "2") (pinfunction "2_2") (pintype "passive"))
      (node (ref "C20") (pin "1") (pinfunction "1_1") (pintype "passive"))
      (node (ref "C21") (pin "1") (pinfunction "1_1") (pintype "passive"))
      (node (ref "C3") (pin "1") (pinfunction "1_1") (pintype "passive"))
      (node (ref "C4") (pin "2") (pinfunction "2_2") (pintype "passive"))
      (node (ref "C5") (pin "2") (pinfunction "2_2") (pintype "passive"))
      (node (ref "C7") (pin "2") (pinfunction "2_2") (pintype "passive"))
      (node (ref "C8") (pin "2") (pinfunction "2_2") (pintype "passive"))
      (node (ref "C9") (pin "2") (pinfunction "GND_2") (pintype "passive"))
      (node (ref "D1") (pin "1") (pinfunction "A_1") (pintype "passive"))
      (node (ref "GT-07") (pin "2") (pinfunction "2_2") (pintype "passive"))
      (node (ref "KEY1") (pin "1") (pinfunction "1_1") (pintype "passive"))
      (node (ref "LED5") (pin "2") (pinfunction "2_2") (pintype "passive"))
      (node (ref "LED6") (pin "2") (pinfunction "2_2") (pintype "passive"))
      (node (ref "MOTOR1") (pin "3") (pinfunction "3_3") (pintype "passive"))
      (node (ref "MOTOR2") (pin "3") (pinfunction "3_3") (pintype "passive"))
      (node (ref "MOTOR3") (pin "3") (pinfunction "3_3") (pintype "passive"))
      (node (ref "MOTOR4") (pin "3") (pinfunction "3_3") (pintype "passive"))
      (node (ref "MP1584EN") (pin "5") (pinfunction "GND_5") (pintype "passive"))
      (node (ref "MPU9250") (pin "2") (pinfunction "2_2") (pintype "passive"))
      (node (ref "NRF24L01+") (pin "1") (pinfunction "1_1") (pintype "passive"))
      (node (ref "P0") (pin "2") (pinfunction "2_2") (pintype "passive"))
      (node (ref "R10") (pin "1") (pinfunction "1_1") (pintype "passive"))
      (node (ref "R11") (pin "1") (pinfunction "1_1") (pintype "passive"))
      (node (ref "R12") (pin "1") (pinfunction "1_1") (pintype "passive"))
      (node (ref "R2") (pin "1") (pinfunction "1_1") (pintype "passive"))
      (node (ref "R3") (pin "1") (pinfunction "1_1") (pintype "passive"))
      (node (ref "SWD") (pin "3") (pinfunction "3_3") (pintype "passive"))
      (node (ref "fatmouse") (pin "10") (pinfunction "VSS_10") (pintype "passive"))
      (node (ref "fatmouse") (pin "20") (pinfunction "VSSA_20") (pintype "passive"))
      (node (ref "fatmouse") (pin "27") (pinfunction "VSS_27") (pintype "passive"))
      (node (ref "fatmouse") (pin "74") (pinfunction "VSS_74") (pintype "passive"))
      (node (ref "fatmouse") (pin "99") (pinfunction "VSS_99") (pintype "passive"))
    )
    (net (code "42") (name "Net-(C16-Pad1)") (class "Default")
      (node (ref "C16") (pin "1") (pinfunction "1_1") (pintype "passive"))
      (node (ref "R12") (pin "2") (pinfunction "2_2") (pintype "passive"))
    )
    (net (code "43") (name "Net-(LED0-Pad1)") (class "Default")
      (node (ref "LED0") (pin "1") (pinfunction "1_1") (pintype "passive"))
      (node (ref "R5") (pin "1") (pinfunction "1_1") (pintype "passive"))
    )
    (net (code "44") (name "Net-(LED1-Pad1)") (class "Default")
      (node (ref "LED1") (pin "1") (pinfunction "1_1") (pintype "passive"))
      (node (ref "R6") (pin "1") (pinfunction "1_1") (pintype "passive"))
    )
    (net (code "45") (name "Net-(LED2-Pad1)") (class "Default")
      (node (ref "LED2") (pin "1") (pinfunction "1_1") (pintype "passive"))
      (node (ref "R7") (pin "1") (pinfunction "1_1") (pintype "passive"))
    )
    (net (code "46") (name "Net-(LED3-Pad1)") (class "Default")
      (node (ref "LED3") (pin "1") (pinfunction "1_1") (pintype "passive"))
      (node (ref "R8") (pin "1") (pinfunction "1_1") (pintype "passive"))
    )
    (net (code "47") (name "unconnected-(BMP280-Pad5)") (class "Default")
      (node (ref "BMP280") (pin "5") (pinfunction "5_5") (pintype "passive+no_connect"))
    )
    (net (code "48") (name "unconnected-(GT-07-Pad5)") (class "Default")
      (node (ref "GT-07") (pin "5") (pinfunction "5_5") (pintype "passive+no_connect"))
    )
    (net (code "49") (name "unconnected-(MOTOR1-Pad2)") (class "Default")
      (node (ref "MOTOR1") (pin "2") (pinfunction "2_2") (pintype "passive+no_connect"))
    )
    (net (code "50") (name "unconnected-(MOTOR2-Pad2)") (class "Default")
      (node (ref "MOTOR2") (pin "2") (pinfunction "2_2") (pintype "passive+no_connect"))
    )
    (net (code "51") (name "unconnected-(MOTOR3-Pad2)") (class "Default")
      (node (ref "MOTOR3") (pin "2") (pinfunction "2_2") (pintype "passive+no_connect"))
    )
    (net (code "52") (name "unconnected-(MOTOR4-Pad2)") (class "Default")
      (node (ref "MOTOR4") (pin "2") (pinfunction "2_2") (pintype "passive+no_connect"))
    )
    (net (code "53") (name "unconnected-(fatmouse-PA0-WKUP_{slash}_UART4_TX_{slash}_TIM2_CH1_ETR{slash}_TIM5_CH1_{slash}_TIM8_ETR_{slash}_ADC123_IN0-Pad23)") (class "Default")
      (node (ref "fatmouse") (pin "23") (pinfunction "PA0-WKUP_/_UART4_TX_/_TIM2_CH1_ETR/_TIM5_CH1_/_TIM8_ETR_/_ADC123_IN0_23") (pintype "passive+no_connect"))
    )
    (net (code "54") (name "unconnected-(fatmouse-PA1_{slash}_TIM5_CH2_{slash}_UART4_RX_{slash}_ADC123_IN1-Pad24)") (class "Default")
      (node (ref "fatmouse") (pin "24") (pinfunction "PA1_/_TIM5_CH2_/_UART4_RX_/_ADC123_IN1_24") (pintype "passive+no_connect"))
    )
    (net (code "55") (name "unconnected-(fatmouse-PA4_{slash}_SPI1_NSS_{slash}_SPI3_NSS_{slash}_USART2_CK_{slash}_ADC12_IN4_{slash}_DAC1_OUT-Pad29)") (class "Default")
      (node (ref "fatmouse") (pin "29") (pinfunction "PA4_/_SPI1_NSS_/_SPI3_NSS_/_USART2_CK_/_ADC12_IN4_/_DAC1_OUT_29") (pintype "passive+no_connect"))
    )
    (net (code "56") (name "unconnected-(fatmouse-PA8_{slash}_USART1_CK_{slash}_I2C3_SCL_{slash}_TIM1_CH1-Pad67)") (class "Default")
      (node (ref "fatmouse") (pin "67") (pinfunction "PA8_/_USART1_CK_/_I2C3_SCL_/_TIM1_CH1_67") (pintype "passive+no_connect"))
    )
    (net (code "57") (name "unconnected-(fatmouse-PA11_{slash}_TIM1_CH4-Pad70)") (class "Default")
      (node (ref "fatmouse") (pin "70") (pinfunction "PA11_/_TIM1_CH4_70") (pintype "passive+no_connect"))
    )
    (net (code "58") (name "unconnected-(fatmouse-PA12_{slash}_TIM1_ETR-Pad71)") (class "Default")
      (node (ref "fatmouse") (pin "71") (pinfunction "PA12_/_TIM1_ETR_71") (pintype "passive+no_connect"))
    )
    (net (code "59") (name "unconnected-(fatmouse-PA15_{slash}_SPI3_NSS_{slash}_TIM2_CH1_ETR-Pad77)") (class "Default")
      (node (ref "fatmouse") (pin "77") (pinfunction "PA15_/_SPI3_NSS_/_TIM2_CH1_ETR_77") (pintype "passive+no_connect"))
    )
    (net (code "60") (name "unconnected-(fatmouse-PB1_{slash}_TIM3_CH4_{slash}_TIM8_CH3N{slash}_TIM1_CH3N_{slash}_ADC12_IN9-Pad36)") (class "Default")
      (node (ref "fatmouse") (pin "36") (pinfunction "PB1_/_TIM3_CH4_/_TIM8_CH3N/_TIM1_CH3N_/_ADC12_IN9_36") (pintype "passive+no_connect"))
    )
    (net (code "61") (name "unconnected-(fatmouse-PB3_{slash}_SPI3_SCK_{slash}_TIM2_CH2_{slash}_SPI1_SCK-Pad89)") (class "Default")
      (node (ref "fatmouse") (pin "89") (pinfunction "PB3_/_SPI3_SCK_/_TIM2_CH2_/_SPI1_SCK_89") (pintype "passive+no_connect"))
    )
    (net (code "62") (name "unconnected-(fatmouse-PB4_{slash}_SPI3_MISO_{slash}_TIM3_CH1_{slash}_SPI1_MISO-Pad90)") (class "Default")
      (node (ref "fatmouse") (pin "90") (pinfunction "PB4_/_SPI3_MISO_/_TIM3_CH1_/_SPI1_MISO_90") (pintype "passive+no_connect"))
    )
    (net (code "63") (name "unconnected-(fatmouse-PB5_{slash}_SPI3_MOSI_{slash}_TIM3_CH2_{slash}_SPI1_MOSI-Pad91)") (class "Default")
      (node (ref "fatmouse") (pin "91") (pinfunction "PB5_/_SPI3_MOSI_/_TIM3_CH2_/_SPI1_MOSI_91") (pintype "passive+no_connect"))
    )
    (net (code "64") (name "unconnected-(fatmouse-PB8_{slash}_TIM4_CH3_{slash}_TIM10_CH1-Pad95)") (class "Default")
      (node (ref "fatmouse") (pin "95") (pinfunction "PB8_/_TIM4_CH3_/_TIM10_CH1_95") (pintype "passive+no_connect"))
    )
    (net (code "65") (name "unconnected-(fatmouse-PB9_{slash}_TIM4_CH4{slash}_TIM11_CH1-Pad96)") (class "Default")
      (node (ref "fatmouse") (pin "96") (pinfunction "PB9_/_TIM4_CH4/_TIM11_CH1_96") (pintype "passive+no_connect"))
    )
    (net (code "66") (name "unconnected-(fatmouse-PB10_{slash}_I2C2_SCL_{slash}_USART3_TX_{slash}_TIM2_CH3_{slash}_SPI2_SCK-Pad47)") (class "Default")
      (node (ref "fatmouse") (pin "47") (pinfunction "PB10_/_I2C2_SCL_/_USART3_TX_/_TIM2_CH3_/_SPI2_SCK_47") (pintype "passive+no_connect"))
    )
    (net (code "67") (name "unconnected-(fatmouse-PB11_{slash}_I2C2_SDA_{slash}_USART3_RX_{slash}_TIM2_CH4-Pad48)") (class "Default")
      (node (ref "fatmouse") (pin "48") (pinfunction "PB11_/_I2C2_SDA_/_USART3_RX_/_TIM2_CH4_48") (pintype "passive+no_connect"))
    )
    (net (code "68") (name "unconnected-(fatmouse-PB12_{slash}_SPI2_NSS_{slash}_USART3_CK_{slash}__CAN2_RX-Pad51)") (class "Default")
      (node (ref "fatmouse") (pin "51") (pinfunction "PB12_/_SPI2_NSS_/_USART3_CK_/__CAN2_RX_51") (pintype "passive+no_connect"))
    )
    (net (code "69") (name "unconnected-(fatmouse-PB13_{slash}_SPI2_SCK_{slash}_TIM1_CH1N_{slash}_CAN2_TX-Pad52)") (class "Default")
      (node (ref "fatmouse") (pin "52") (pinfunction "PB13_/_SPI2_SCK_/_TIM1_CH1N_/_CAN2_TX_52") (pintype "passive+no_connect"))
    )
    (net (code "70") (name "unconnected-(fatmouse-PC0_{slash}_ADC123_IN10-Pad15)") (class "Default")
      (node (ref "fatmouse") (pin "15") (pinfunction "PC0_/_ADC123_IN10_15") (pintype "passive+no_connect"))
    )
    (net (code "71") (name "unconnected-(fatmouse-PC1_{slash}_ADC123_IN11-Pad16)") (class "Default")
      (node (ref "fatmouse") (pin "16") (pinfunction "PC1_/_ADC123_IN11_16") (pintype "passive+no_connect"))
    )
    (net (code "72") (name "unconnected-(fatmouse-PC2_{slash}_SPI2_MISO_{slash}_ADC123_IN12-Pad17)") (class "Default")
      (node (ref "fatmouse") (pin "17") (pinfunction "PC2_/_SPI2_MISO_/_ADC123_IN12_17") (pintype "passive+no_connect"))
    )
    (net (code "73") (name "unconnected-(fatmouse-PC3_{slash}_SPI2_MOSI_{slash}_ADC123_IN13-Pad18)") (class "Default")
      (node (ref "fatmouse") (pin "18") (pinfunction "PC3_/_SPI2_MOSI_/_ADC123_IN13_18") (pintype "passive+no_connect"))
    )
    (net (code "74") (name "unconnected-(fatmouse-PC6_{slash}_TIM8_CH1_{slash}_USART6_TX_{slash}_TIM3_CH1-Pad63)") (class "Default")
      (node (ref "fatmouse") (pin "63") (pinfunction "PC6_/_TIM8_CH1_/_USART6_TX_/_TIM3_CH1_63") (pintype "passive+no_connect"))
    )
    (net (code "75") (name "unconnected-(fatmouse-PC7_{slash}_TIM8_CH2_{slash}_USART6_RX_{slash}_TIM3_CH2-Pad64)") (class "Default")
      (node (ref "fatmouse") (pin "64") (pinfunction "PC7_/_TIM8_CH2_/_USART6_RX_/_TIM3_CH2_64") (pintype "passive+no_connect"))
    )
    (net (code "76") (name "unconnected-(fatmouse-PC8_{slash}_TIM8_CH3_{slash}_USART6_CK_{slash}_TIM3_CH3-Pad65)") (class "Default")
      (node (ref "fatmouse") (pin "65") (pinfunction "PC8_/_TIM8_CH3_/_USART6_CK_/_TIM3_CH3_65") (pintype "passive+no_connect"))
    )
    (net (code "77") (name "unconnected-(fatmouse-PC9_{slash}_TIM8_CH4_{slash}_I2C3_SDA_{slash}_TIM3_CH4-Pad66)") (class "Default")
      (node (ref "fatmouse") (pin "66") (pinfunction "PC9_/_TIM8_CH4_/_I2C3_SDA_/_TIM3_CH4_66") (pintype "passive+no_connect"))
    )
    (net (code "78") (name "unconnected-(fatmouse-PC10_{slash}_UART4_TX_{slash}_SPI3_SCK_{slash}_USART3_TX-Pad78)") (class "Default")
      (node (ref "fatmouse") (pin "78") (pinfunction "PC10_/_UART4_TX_/_SPI3_SCK_/_USART3_TX_78") (pintype "passive+no_connect"))
    )
    (net (code "79") (name "unconnected-(fatmouse-PC11_{slash}_UART4_RX_{slash}_SPI3_MISO_{slash}_USART3_RX-Pad79)") (class "Default")
      (node (ref "fatmouse") (pin "79") (pinfunction "PC11_/_UART4_RX_/_SPI3_MISO_/_USART3_RX_79") (pintype "passive+no_connect"))
    )
    (net (code "80") (name "unconnected-(fatmouse-PC12_{slash}_UART5_TX_{slash}_SPI3_MOSI_{slash}_USART3_CK-Pad80)") (class "Default")
      (node (ref "fatmouse") (pin "80") (pinfunction "PC12_/_UART5_TX_/_SPI3_MOSI_/_USART3_CK_80") (pintype "passive+no_connect"))
    )
    (net (code "81") (name "unconnected-(fatmouse-PC13-Pad7)") (class "Default")
      (node (ref "fatmouse") (pin "7") (pinfunction "PC13_7") (pintype "passive+no_connect"))
    )
    (net (code "82") (name "unconnected-(fatmouse-PC14-OSC32_IN-Pad8)") (class "Default")
      (node (ref "fatmouse") (pin "8") (pinfunction "PC14-OSC32_IN_8") (pintype "passive+no_connect"))
    )
    (net (code "83") (name "unconnected-(fatmouse-PC15-OSC32_OUT-Pad9)") (class "Default")
      (node (ref "fatmouse") (pin "9") (pinfunction "PC15-OSC32_OUT_9") (pintype "passive+no_connect"))
    )
    (net (code "84") (name "unconnected-(fatmouse-PD0_{slash}_CAN1_RX-Pad81)") (class "Default")
      (node (ref "fatmouse") (pin "81") (pinfunction "PD0_/_CAN1_RX_81") (pintype "passive+no_connect"))
    )
    (net (code "85") (name "unconnected-(fatmouse-PD1_{slash}_CAN1_TX-Pad82)") (class "Default")
      (node (ref "fatmouse") (pin "82") (pinfunction "PD1_/_CAN1_TX_82") (pintype "passive+no_connect"))
    )
    (net (code "86") (name "unconnected-(fatmouse-PD2_{slash}_TIM3_ETR_{slash}_UART5_RX-Pad83)") (class "Default")
      (node (ref "fatmouse") (pin "83") (pinfunction "PD2_/_TIM3_ETR_/_UART5_RX_83") (pintype "passive+no_connect"))
    )
    (net (code "87") (name "unconnected-(fatmouse-PD3-Pad84)") (class "Default")
      (node (ref "fatmouse") (pin "84") (pinfunction "PD3_84") (pintype "passive+no_connect"))
    )
    (net (code "88") (name "unconnected-(fatmouse-PD4-Pad85)") (class "Default")
      (node (ref "fatmouse") (pin "85") (pinfunction "PD4_85") (pintype "passive+no_connect"))
    )
    (net (code "89") (name "unconnected-(fatmouse-PD5_{slash}_USART2_TX-Pad86)") (class "Default")
      (node (ref "fatmouse") (pin "86") (pinfunction "PD5_/_USART2_TX_86") (pintype "passive+no_connect"))
    )
    (net (code "90") (name "unconnected-(fatmouse-PD6_{slash}_USART2_RX-Pad87)") (class "Default")
      (node (ref "fatmouse") (pin "87") (pinfunction "PD6_/_USART2_RX_87") (pintype "passive+no_connect"))
    )
    (net (code "91") (name "unconnected-(fatmouse-PD7_{slash}_USART2_CK-Pad88)") (class "Default")
      (node (ref "fatmouse") (pin "88") (pinfunction "PD7_/_USART2_CK_88") (pintype "passive+no_connect"))
    )
    (net (code "92") (name "unconnected-(fatmouse-PD8_{slash}__USART3_TX-Pad55)") (class "Default")
      (node (ref "fatmouse") (pin "55") (pinfunction "PD8_/__USART3_TX_55") (pintype "passive+no_connect"))
    )
    (net (code "93") (name "unconnected-(fatmouse-PD9_{slash}_USART3_RX-Pad56)") (class "Default")
      (node (ref "fatmouse") (pin "56") (pinfunction "PD9_/_USART3_RX_56") (pintype "passive+no_connect"))
    )
    (net (code "94") (name "unconnected-(fatmouse-PD14_{slash}_TIM4_CH3-Pad61)") (class "Default")
      (node (ref "fatmouse") (pin "61") (pinfunction "PD14_/_TIM4_CH3_61") (pintype "passive+no_connect"))
    )
    (net (code "95") (name "unconnected-(fatmouse-PD15_{slash}_TIM4_CH4-Pad62)") (class "Default")
      (node (ref "fatmouse") (pin "62") (pinfunction "PD15_/_TIM4_CH4_62") (pintype "passive+no_connect"))
    )
    (net (code "96") (name "unconnected-(fatmouse-PE0-Pad97)") (class "Default")
      (node (ref "fatmouse") (pin "97") (pinfunction "PE0_97") (pintype "passive+no_connect"))
    )
    (net (code "97") (name "unconnected-(fatmouse-PE1-Pad98)") (class "Default")
      (node (ref "fatmouse") (pin "98") (pinfunction "PE1_98") (pintype "passive+no_connect"))
    )
    (net (code "98") (name "unconnected-(fatmouse-PE2-Pad1)") (class "Default")
      (node (ref "fatmouse") (pin "1") (pinfunction "PE2_1") (pintype "passive+no_connect"))
    )
    (net (code "99") (name "unconnected-(fatmouse-PE3-Pad2)") (class "Default")
      (node (ref "fatmouse") (pin "2") (pinfunction "PE3_2") (pintype "passive+no_connect"))
    )
    (net (code "100") (name "unconnected-(fatmouse-PE4-Pad3)") (class "Default")
      (node (ref "fatmouse") (pin "3") (pinfunction "PE4_3") (pintype "passive+no_connect"))
    )
    (net (code "101") (name "unconnected-(fatmouse-PE5_{slash}_TIM9_CH1-Pad4)") (class "Default")
      (node (ref "fatmouse") (pin "4") (pinfunction "PE5_/_TIM9_CH1_4") (pintype "passive+no_connect"))
    )
    (net (code "102") (name "unconnected-(fatmouse-PE6_{slash}_TIM9_CH2-Pad5)") (class "Default")
      (node (ref "fatmouse") (pin "5") (pinfunction "PE6_/_TIM9_CH2_5") (pintype "passive+no_connect"))
    )
    (net (code "103") (name "unconnected-(fatmouse-PE7_{slash}_TIM1_ETR-Pad38)") (class "Default")
      (node (ref "fatmouse") (pin "38") (pinfunction "PE7_/_TIM1_ETR_38") (pintype "passive+no_connect"))
    )
    (net (code "104") (name "unconnected-(fatmouse-PE8_{slash}_TIM1_CH1N-Pad39)") (class "Default")
      (node (ref "fatmouse") (pin "39") (pinfunction "PE8_/_TIM1_CH1N_39") (pintype "passive+no_connect"))
    )
    (net (code "105") (name "unconnected-(fatmouse-PE10_{slash}_TIM1_CH2N-Pad41)") (class "Default")
      (node (ref "fatmouse") (pin "41") (pinfunction "PE10_/_TIM1_CH2N_41") (pintype "passive+no_connect"))
    )
    (net (code "106") (name "unconnected-(fatmouse-PE12_{slash}_TIM1_CH3N-Pad43)") (class "Default")
      (node (ref "fatmouse") (pin "43") (pinfunction "PE12_/_TIM1_CH3N_43") (pintype "passive+no_connect"))
    )
    (net (code "107") (name "unconnected-(fatmouse-PE15-Pad46)") (class "Default")
      (node (ref "fatmouse") (pin "46") (pinfunction "PE15_46") (pintype "passive+no_connect"))
    )
  )
)
